# HC_SR04_SCH.net
KiCad netlist of a schematic drawn in Altium Designer
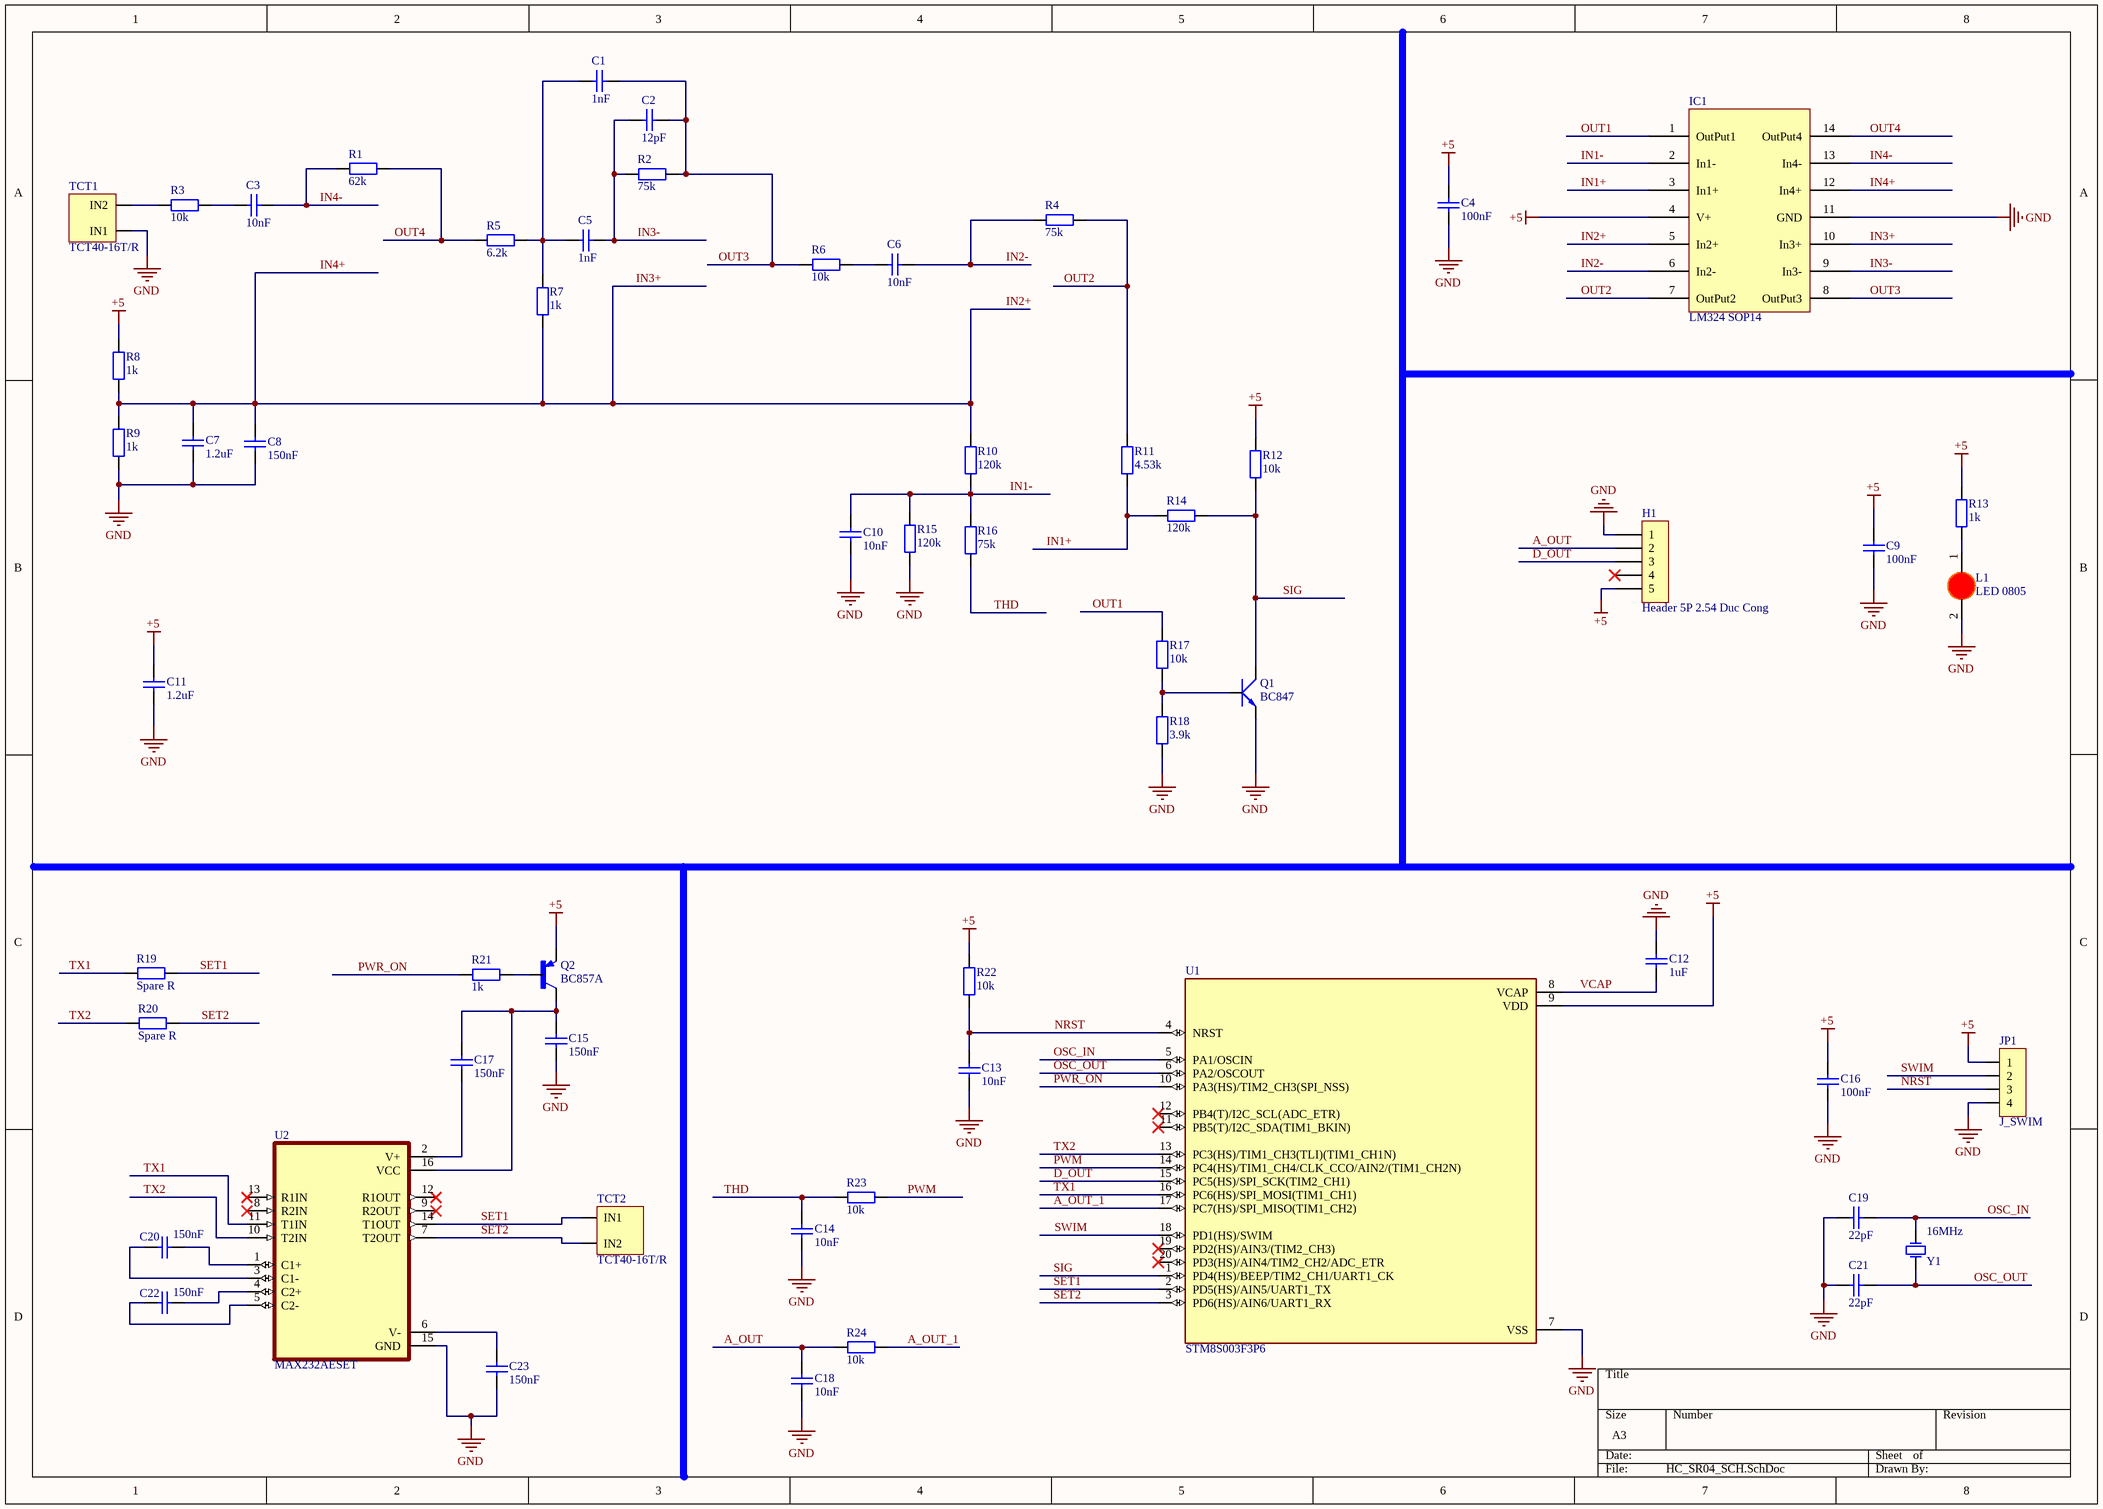
[diagram p0: HC_SR04_SCH.SchDoc]

(export (version "E")
  (design (tool "Eeschema 10.0.6"))
  (components
    (comp (ref "C1")
      (value "1nF")
      (footprint "tu 0603")
      (description "Dán")
      (libsource (lib "namnt_Lib") (part "Tu 0603 102 50V 10%"))
    )
    (comp (ref "C2")
      (value "12pF")
      (footprint "tu 0603")
      (description "Dán")
      (libsource (lib "namnt_Lib") (part "Tu 0603 102 50V 10%"))
    )
    (comp (ref "C3")
      (value "10nF")
      (footprint "tu 0603")
      (description "Dán")
      (libsource (lib "namnt_Lib") (part "Tu 0603 103 50V 10%"))
    )
    (comp (ref "C4")
      (value "100nF")
      (footprint "tu 0603")
      (description "Dán")
      (libsource (lib "namnt_Lib") (part "Tu 0603 102 50V 10%"))
    )
    (comp (ref "C5")
      (value "1nF")
      (footprint "tu 0603")
      (description "Dán")
      (libsource (lib "namnt_Lib") (part "Tu 0603 102 50V 10%"))
    )
    (comp (ref "C6")
      (value "10nF")
      (footprint "tu 0603")
      (description "Dán")
      (libsource (lib "namnt_Lib") (part "Tu 0603 102 50V 10%"))
    )
    (comp (ref "C7")
      (value "1.2uF")
      (footprint "tu 0603")
      (description "Dán")
      (libsource (lib "namnt_Lib") (part "Tu 0603 104 50V 10%"))
    )
    (comp (ref "C8")
      (value "150nF")
      (footprint "tu 0603")
      (description "Dán")
      (libsource (lib "namnt_Lib") (part "Tu 0603 104 50V 10%"))
    )
    (comp (ref "C9")
      (value "100nF")
      (footprint "tu 0603")
      (description "Dán")
      (libsource (lib "namnt_Lib") (part "Tu 0603 102 50V 10%"))
    )
    (comp (ref "C10")
      (value "10nF")
      (footprint "tu 0603")
      (description "Dán")
      (libsource (lib "namnt_Lib") (part "Tu 0603 102 50V 10%"))
    )
    (comp (ref "C11")
      (value "1.2uF")
      (footprint "tu 0603")
      (description "Dán")
      (libsource (lib "namnt_Lib") (part "Tu 0603 102 50V 10%"))
    )
    (comp (ref "C12")
      (value "1uF")
      (footprint "tu 0603")
      (description "Dán")
      (libsource (lib "namnt_Lib") (part "Tu 0603 102 50V 10%"))
    )
    (comp (ref "C13")
      (value "10nF")
      (footprint "tu 0603")
      (description "Dán")
      (libsource (lib "namnt_Lib") (part "Tu 0603 102 50V 10%"))
    )
    (comp (ref "C14")
      (value "10nF")
      (footprint "tu 0603")
      (description "Dán")
      (libsource (lib "namnt_Lib") (part "Tu 0603 102 50V 10%"))
    )
    (comp (ref "C15")
      (value "150nF")
      (footprint "tu 0603")
      (description "Dán")
      (libsource (lib "namnt_Lib") (part "Tu 0603 102 50V 10%"))
    )
    (comp (ref "C16")
      (value "100nF")
      (footprint "tu 0603")
      (description "Dán")
      (libsource (lib "namnt_Lib") (part "Tu 0603 102 50V 10%"))
    )
    (comp (ref "C17")
      (value "150nF")
      (footprint "tu 0603")
      (description "Dán")
      (libsource (lib "namnt_Lib") (part "Tu 0603 102 50V 10%"))
    )
    (comp (ref "C18")
      (value "10nF")
      (footprint "tu 0603")
      (description "Dán")
      (libsource (lib "namnt_Lib") (part "Tu 0603 102 50V 10%"))
    )
    (comp (ref "C19")
      (value "22pF")
      (footprint "tu 0603")
      (description "Dán")
      (libsource (lib "namnt_Lib") (part "Tu 0603 102 50V 10%"))
    )
    (comp (ref "C20")
      (value "150nF")
      (footprint "tu 0603")
      (description "Dán")
      (libsource (lib "namnt_Lib") (part "Tu 0603 102 50V 10%"))
    )
    (comp (ref "C21")
      (value "22pF")
      (footprint "tu 0603")
      (description "Dán")
      (libsource (lib "namnt_Lib") (part "Tu 0603 102 50V 10%"))
    )
    (comp (ref "C22")
      (value "150nF")
      (footprint "tu 0603")
      (description "Dán")
      (libsource (lib "namnt_Lib") (part "Tu 0603 102 50V 10%"))
    )
    (comp (ref "C23")
      (value "150nF")
      (footprint "tu 0603")
      (description "Dán")
      (libsource (lib "namnt_Lib") (part "Tu 0603 102 50V 10%"))
    )
    (comp (ref "H1")
      (value "Header 5P 2.54 Duc Cong")
      (footprint "Header 5P DC 2.54")
      (description "Cắm")
      (libsource (lib "namnt_Lib") (part "Header 5P 2.54 Duc Cong"))
    )
    (comp (ref "IC1")
      (value "LM324 SOP14")
      (footprint "sop 14")
      (description "Dán")
      (libsource (lib "namnt_Lib") (part "LM324 SOP14"))
    )
    (comp (ref "JP1")
      (value "J_SWIM")
      (footprint "JP 1x4 DT")
      (description "Cắm")
      (libsource (lib "namnt_Lib") (part "JP 1x4 2.54 Duc Thang"))
    )
    (comp (ref "L1")
      (value "LED 0805")
      (footprint "LED-0805-Red")
      (description "Dán")
      (libsource (lib "namnt_Lib") (part "LED 0805 Do"))
    )
    (comp (ref "Q1")
      (value "BC847")
      (footprint "SOT-23")
      (description "SOT-23")
      (libsource (lib "namnt_Lib") (part "Trans BC817"))
    )
    (comp (ref "Q2")
      (value "BC857A")
      (footprint "TRANS_BC857A_RFG")
      (description "SOT-23, 200mW, PNP Bipolar Transistor")
      (fields (field (name "MF") "Taiwan Semiconductor") (field (name "MP") "BC857A RFG"))
      (libsource (lib "namnt_Lib") (part "BC857A_RFG"))
    )
    (comp (ref "R1")
      (value "62k")
      (footprint "tro smd 0603")
      (description "Dán")
      (libsource (lib "namnt_Lib") (part "Tro 0603 1% 1k"))
    )
    (comp (ref "R2")
      (value "75k")
      (footprint "tro smd 0603")
      (description "Dán")
      (libsource (lib "namnt_Lib") (part "Tro 0603 1% 1k"))
    )
    (comp (ref "R3")
      (value "10k")
      (footprint "tro smd 0603")
      (description "Dán")
      (libsource (lib "namnt_Lib") (part "Tro 0603 1% 10k"))
    )
    (comp (ref "R4")
      (value "75k")
      (footprint "tro smd 0603")
      (description "Dán")
      (libsource (lib "namnt_Lib") (part "Tro 0603 1% 1k"))
    )
    (comp (ref "R5")
      (value "6.2k")
      (footprint "tro smd 0603")
      (description "Dán")
      (libsource (lib "namnt_Lib") (part "Tro 0603 1% 1k"))
    )
    (comp (ref "R6")
      (value "10k")
      (footprint "tro smd 0603")
      (description "Dán")
      (libsource (lib "namnt_Lib") (part "Tro 0603 1% 1k"))
    )
    (comp (ref "R7")
      (value "1k")
      (footprint "tro smd 0603")
      (description "Dán")
      (libsource (lib "namnt_Lib") (part "Tro 0603 1% 1k"))
    )
    (comp (ref "R8")
      (value "1k")
      (footprint "tro smd 0603")
      (description "Dán")
      (libsource (lib "namnt_Lib") (part "Tro 0603 1% 1k"))
    )
    (comp (ref "R9")
      (value "1k")
      (footprint "tro smd 0603")
      (description "Dán")
      (libsource (lib "namnt_Lib") (part "Tro 0603 1% 1k"))
    )
    (comp (ref "R10")
      (value "120k")
      (footprint "tro smd 0603")
      (description "Dán")
      (libsource (lib "namnt_Lib") (part "Tro 0603 1% 1k"))
    )
    (comp (ref "R11")
      (value "4.53k")
      (footprint "tro smd 0603")
      (description "Dán")
      (libsource (lib "namnt_Lib") (part "Tro 0603 1% 1k"))
    )
    (comp (ref "R12")
      (value "10k")
      (footprint "tro smd 0603")
      (description "Dán")
      (libsource (lib "namnt_Lib") (part "Tro 0603 1% 1k"))
    )
    (comp (ref "R13")
      (value "1k")
      (footprint "tro smd 0603")
      (description "Dán")
      (libsource (lib "namnt_Lib") (part "Tro 0603 1% 1k"))
    )
    (comp (ref "R14")
      (value "120k")
      (footprint "tro smd 0603")
      (description "Dán")
      (libsource (lib "namnt_Lib") (part "Tro 0603 1% 1k"))
    )
    (comp (ref "R15")
      (value "120k")
      (footprint "tro smd 0603")
      (description "Dán")
      (libsource (lib "namnt_Lib") (part "Tro 0603 1% 1k"))
    )
    (comp (ref "R16")
      (value "75k")
      (footprint "tro smd 0603")
      (description "Dán")
      (libsource (lib "namnt_Lib") (part "Tro 0603 1% 1k"))
    )
    (comp (ref "R17")
      (value "10k")
      (footprint "tro smd 0603")
      (description "Dán")
      (libsource (lib "namnt_Lib") (part "Tro 0603 1% 1k"))
    )
    (comp (ref "R18")
      (value "3.9k")
      (footprint "tro smd 0603")
      (description "Dán")
      (libsource (lib "namnt_Lib") (part "Tro 0603 1% 1k"))
    )
    (comp (ref "R19")
      (value "Spare R")
      (footprint "tro smd 0603")
      (description "Dán")
      (libsource (lib "namnt_Lib") (part "Tro 0603 1% 1k"))
    )
    (comp (ref "R20")
      (value "Spare R")
      (footprint "tro smd 0603")
      (description "Dán")
      (libsource (lib "namnt_Lib") (part "Tro 0603 1% 1k"))
    )
    (comp (ref "R21")
      (value "1k")
      (footprint "tro smd 0603")
      (description "Dán")
      (libsource (lib "namnt_Lib") (part "Tro 0603 1% 1k"))
    )
    (comp (ref "R22")
      (value "10k")
      (footprint "tro smd 0603")
      (description "Dán")
      (libsource (lib "namnt_Lib") (part "Tro 0603 1% 1k"))
    )
    (comp (ref "R23")
      (value "10k")
      (footprint "tro smd 0603")
      (description "Dán")
      (libsource (lib "namnt_Lib") (part "Tro 0603 1% 1k"))
    )
    (comp (ref "R24")
      (value "10k")
      (footprint "tro smd 0603")
      (description "Dán")
      (libsource (lib "namnt_Lib") (part "Tro 0603 1% 1k"))
    )
    (comp (ref "TCT1")
      (value "TCT40-16T/R")
      (footprint "TCT40")
      (description "Piezoelectric Ceramic Ultrasonic Sensor")
      (libsource (lib "") (part "TCT40-16T/R_1"))
    )
    (comp (ref "TCT2")
      (value "TCT40-16T/R")
      (footprint "TCT40")
      (description "Piezoelectric Ceramic Ultrasonic Sensor")
      (libsource (lib "namnt_Lib") (part "TCT40-16T/R"))
    )
    (comp (ref "U1")
      (value "STM8S003F3P6")
      (footprint "SOP65P640X120-20N")
      (description "STM8 series Microcontroller IC 8-Bit 16MHz 8KB (8K x 8) FLASH 20-TSSOP")
      (fields (field (name "MF") "STMicroelectronics"))
      (libsource (lib "namnt_Lib") (part "STM8S003F3P6"))
    )
    (comp (ref "U2")
      (value "MAX232AESET")
      (footprint "SOIC127P600X175-16N")
      (description "Dual Transmitter/Receiver RS-232 16-Pin SOIC N Tube")
      (fields (field (name "MF") "Analog Devices") (field (name "MP") "MAX232AESE+"))
      (libsource (lib "namnt_Lib") (part "MAX232AESET"))
    )
    (comp (ref "Y1")
      (value "16MHz")
      (footprint "THACH ANH DAN 3215")
      (description "C700805")
      (libsource (lib "namnt_Lib") (part "Thach Anh SMD 3225"))
    )
  )
  (nets
    (net (code "1") (name "+5") (class "Default")
      (node (ref "C11") (pin "1") (pinfunction "1_1") (pintype "passive"))
      (node (ref "C16") (pin "1") (pinfunction "1_1") (pintype "passive"))
      (node (ref "C4") (pin "1") (pinfunction "1_1") (pintype "passive"))
      (node (ref "C9") (pin "1") (pinfunction "1_1") (pintype "passive"))
      (node (ref "H1") (pin "5") (pinfunction "5_5") (pintype "passive"))
      (node (ref "IC1") (pin "4") (pinfunction "V+_4") (pintype "passive"))
      (node (ref "JP1") (pin "1") (pinfunction "1_1") (pintype "passive"))
      (node (ref "Q2") (pin "2") (pinfunction "E_2") (pintype "passive"))
      (node (ref "R12") (pin "2") (pinfunction "2_2") (pintype "passive"))
      (node (ref "R13") (pin "2") (pinfunction "2_2") (pintype "passive"))
      (node (ref "R22") (pin "1") (pinfunction "1_1") (pintype "passive"))
      (node (ref "R8") (pin "2") (pinfunction "2_2") (pintype "passive"))
      (node (ref "U1") (pin "9") (pinfunction "VDD_9") (pintype "power_in"))
    )
    (net (code "2") (name "/A_OUT") (class "Default")
      (node (ref "C18") (pin "1") (pinfunction "1_1") (pintype "passive"))
      (node (ref "H1") (pin "2") (pinfunction "2_2") (pintype "passive"))
      (node (ref "R24") (pin "2") (pinfunction "2_2") (pintype "passive"))
    )
    (net (code "3") (name "/A_OUT_1") (class "Default")
      (node (ref "R24") (pin "1") (pinfunction "1_1") (pintype "passive"))
      (node (ref "U1") (pin "17") (pinfunction "PC7(HS)/SPI_MISO(TIM1_CH2)_17") (pintype "bidirectional"))
    )
    (net (code "4") (name "/D_OUT") (class "Default")
      (node (ref "H1") (pin "3") (pinfunction "3_3") (pintype "passive"))
      (node (ref "U1") (pin "15") (pinfunction "PC5(HS)/SPI_SCK(TIM2_CH1)_15") (pintype "bidirectional"))
    )
    (net (code "5") (name "/IN1+") (class "Default")
      (node (ref "IC1") (pin "3") (pinfunction "In1+_3") (pintype "passive"))
      (node (ref "R11") (pin "2") (pinfunction "2_2") (pintype "passive"))
      (node (ref "R14") (pin "1") (pinfunction "1_1") (pintype "passive"))
    )
    (net (code "6") (name "/IN1-") (class "Default")
      (node (ref "C10") (pin "1") (pinfunction "1_1") (pintype "passive"))
      (node (ref "IC1") (pin "2") (pinfunction "In1-_2") (pintype "passive"))
      (node (ref "R10") (pin "2") (pinfunction "2_2") (pintype "passive"))
      (node (ref "R15") (pin "2") (pinfunction "2_2") (pintype "passive"))
      (node (ref "R16") (pin "2") (pinfunction "2_2") (pintype "passive"))
    )
    (net (code "7") (name "/IN2+") (class "Default")
      (node (ref "C7") (pin "1") (pinfunction "1_1") (pintype "passive"))
      (node (ref "C8") (pin "1") (pinfunction "1_1") (pintype "passive"))
      (node (ref "IC1") (pin "10") (pinfunction "In3+_10") (pintype "passive"))
      (node (ref "IC1") (pin "12") (pinfunction "In4+_12") (pintype "passive"))
      (node (ref "IC1") (pin "5") (pinfunction "In2+_5") (pintype "passive"))
      (node (ref "R10") (pin "1") (pinfunction "1_1") (pintype "passive"))
      (node (ref "R7") (pin "2") (pinfunction "2_2") (pintype "passive"))
      (node (ref "R8") (pin "1") (pinfunction "1_1") (pintype "passive"))
      (node (ref "R9") (pin "2") (pinfunction "2_2") (pintype "passive"))
    )
    (net (code "8") (name "/IN2-") (class "Default")
      (node (ref "C6") (pin "1") (pinfunction "1_1") (pintype "passive"))
      (node (ref "IC1") (pin "6") (pinfunction "In2-_6") (pintype "passive"))
      (node (ref "R4") (pin "2") (pinfunction "2_2") (pintype "passive"))
    )
    (net (code "9") (name "/IN3-") (class "Default")
      (node (ref "C2") (pin "2") (pinfunction "2_2") (pintype "passive"))
      (node (ref "C5") (pin "1") (pinfunction "1_1") (pintype "passive"))
      (node (ref "IC1") (pin "9") (pinfunction "In3-_9") (pintype "passive"))
      (node (ref "R2") (pin "2") (pinfunction "2_2") (pintype "passive"))
    )
    (net (code "10") (name "/IN4-") (class "Default")
      (node (ref "C3") (pin "2") (pinfunction "2_2") (pintype "passive"))
      (node (ref "IC1") (pin "13") (pinfunction "In4-_13") (pintype "passive"))
      (node (ref "R1") (pin "2") (pinfunction "2_2") (pintype "passive"))
    )
    (net (code "11") (name "/NRST") (class "Default")
      (node (ref "C13") (pin "1") (pinfunction "1_1") (pintype "passive"))
      (node (ref "JP1") (pin "3") (pinfunction "3_3") (pintype "passive"))
      (node (ref "R22") (pin "2") (pinfunction "2_2") (pintype "passive"))
      (node (ref "U1") (pin "4") (pinfunction "NRST_4") (pintype "bidirectional"))
    )
    (net (code "12") (name "/OSC_IN") (class "Default")
      (node (ref "C19") (pin "2") (pinfunction "2_2") (pintype "passive"))
      (node (ref "U1") (pin "5") (pinfunction "PA1/OSCIN_5") (pintype "bidirectional"))
      (node (ref "Y1") (pin "2") (pinfunction "OSC2_2") (pintype "passive"))
    )
    (net (code "13") (name "/OSC_OUT") (class "Default")
      (node (ref "C21") (pin "2") (pinfunction "2_2") (pintype "passive"))
      (node (ref "U1") (pin "6") (pinfunction "PA2/OSCOUT_6") (pintype "bidirectional"))
      (node (ref "Y1") (pin "1") (pinfunction "OSC1_1") (pintype "passive"))
    )
    (net (code "14") (name "/OUT1") (class "Default")
      (node (ref "IC1") (pin "1") (pinfunction "OutPut1_1") (pintype "passive"))
      (node (ref "R17") (pin "2") (pinfunction "2_2") (pintype "passive"))
    )
    (net (code "15") (name "/OUT2") (class "Default")
      (node (ref "IC1") (pin "7") (pinfunction "OutPut2_7") (pintype "passive"))
      (node (ref "R11") (pin "1") (pinfunction "1_1") (pintype "passive"))
      (node (ref "R4") (pin "1") (pinfunction "1_1") (pintype "passive"))
    )
    (net (code "16") (name "/OUT3") (class "Default")
      (node (ref "C1") (pin "1") (pinfunction "1_1") (pintype "passive"))
      (node (ref "C2") (pin "1") (pinfunction "1_1") (pintype "passive"))
      (node (ref "IC1") (pin "8") (pinfunction "OutPut3_8") (pintype "passive"))
      (node (ref "R2") (pin "1") (pinfunction "1_1") (pintype "passive"))
      (node (ref "R6") (pin "2") (pinfunction "2_2") (pintype "passive"))
    )
    (net (code "17") (name "/OUT4") (class "Default")
      (node (ref "IC1") (pin "14") (pinfunction "OutPut4_14") (pintype "passive"))
      (node (ref "R1") (pin "1") (pinfunction "1_1") (pintype "passive"))
      (node (ref "R5") (pin "2") (pinfunction "2_2") (pintype "passive"))
    )
    (net (code "18") (name "/PWM") (class "Default")
      (node (ref "R23") (pin "1") (pinfunction "1_1") (pintype "passive"))
      (node (ref "U1") (pin "14") (pinfunction "PC4(HS)/TIM1_CH4/CLK_CCO/AIN2/(TIM1_CH2N)_14") (pintype "bidirectional"))
    )
    (net (code "19") (name "/PWR_ON") (class "Default")
      (node (ref "R21") (pin "2") (pinfunction "2_2") (pintype "passive"))
      (node (ref "U1") (pin "10") (pinfunction "PA3(HS)/TIM2_CH3(SPI_NSS)_10") (pintype "bidirectional"))
    )
    (net (code "20") (name "/SET1") (class "Default")
      (node (ref "R19") (pin "2") (pinfunction "2_2") (pintype "passive"))
      (node (ref "TCT2") (pin "1") (pinfunction "IN1_1") (pintype "passive"))
      (node (ref "U1") (pin "2") (pinfunction "PD5(HS)/AIN5/UART1_TX_2") (pintype "bidirectional"))
      (node (ref "U2") (pin "14") (pinfunction "T1OUT_14") (pintype "output"))
    )
    (net (code "21") (name "/SET2") (class "Default")
      (node (ref "R20") (pin "2") (pinfunction "2_2") (pintype "passive"))
      (node (ref "TCT2") (pin "2") (pinfunction "IN2_2") (pintype "passive"))
      (node (ref "U1") (pin "3") (pinfunction "PD6(HS)/AIN6/UART1_RX_3") (pintype "bidirectional"))
      (node (ref "U2") (pin "7") (pinfunction "T2OUT_7") (pintype "output"))
    )
    (net (code "22") (name "/SIG") (class "Default")
      (node (ref "Q1") (pin "3") (pinfunction "C_3") (pintype "passive"))
      (node (ref "R12") (pin "1") (pinfunction "1_1") (pintype "passive"))
      (node (ref "R14") (pin "2") (pinfunction "2_2") (pintype "passive"))
      (node (ref "U1") (pin "1") (pinfunction "PD4(HS)/BEEP/TIM2_CH1/UART1_CK_1") (pintype "bidirectional"))
    )
    (net (code "23") (name "/SWIM") (class "Default")
      (node (ref "JP1") (pin "2") (pinfunction "2_2") (pintype "passive"))
      (node (ref "U1") (pin "18") (pinfunction "PD1(HS)/SWIM_18") (pintype "bidirectional"))
    )
    (net (code "24") (name "/THD") (class "Default")
      (node (ref "C14") (pin "1") (pinfunction "1_1") (pintype "passive"))
      (node (ref "R16") (pin "1") (pinfunction "1_1") (pintype "passive"))
      (node (ref "R23") (pin "2") (pinfunction "2_2") (pintype "passive"))
    )
    (net (code "25") (name "/TX1") (class "Default")
      (node (ref "R19") (pin "1") (pinfunction "1_1") (pintype "passive"))
      (node (ref "U1") (pin "16") (pinfunction "PC6(HS)/SPI_MOSI(TIM1_CH1)_16") (pintype "bidirectional"))
      (node (ref "U2") (pin "11") (pinfunction "T1IN_11") (pintype "input"))
    )
    (net (code "26") (name "/TX2") (class "Default")
      (node (ref "R20") (pin "1") (pinfunction "1_1") (pintype "passive"))
      (node (ref "U1") (pin "13") (pinfunction "PC3(HS)/TIM1_CH3(TLI)(TIM1_CH1N)_13") (pintype "bidirectional"))
      (node (ref "U2") (pin "10") (pinfunction "T2IN_10") (pintype "input"))
    )
    (net (code "27") (name "/VCAP") (class "Default")
      (node (ref "C12") (pin "2") (pinfunction "2_2") (pintype "passive"))
      (node (ref "U1") (pin "8") (pinfunction "VCAP_8") (pintype "power_in"))
    )
    (net (code "28") (name "GND") (class "Default")
      (node (ref "C10") (pin "2") (pinfunction "2_2") (pintype "passive"))
      (node (ref "C11") (pin "2") (pinfunction "2_2") (pintype "passive"))
      (node (ref "C12") (pin "1") (pinfunction "1_1") (pintype "passive"))
      (node (ref "C13") (pin "2") (pinfunction "2_2") (pintype "passive"))
      (node (ref "C14") (pin "2") (pinfunction "2_2") (pintype "passive"))
      (node (ref "C15") (pin "2") (pinfunction "2_2") (pintype "passive"))
      (node (ref "C16") (pin "2") (pinfunction "2_2") (pintype "passive"))
      (node (ref "C18") (pin "2") (pinfunction "2_2") (pintype "passive"))
      (node (ref "C19") (pin "1") (pinfunction "1_1") (pintype "passive"))
      (node (ref "C21") (pin "1") (pinfunction "1_1") (pintype "passive"))
      (node (ref "C23") (pin "2") (pinfunction "2_2") (pintype "passive"))
      (node (ref "C4") (pin "2") (pinfunction "2_2") (pintype "passive"))
      (node (ref "C7") (pin "2") (pinfunction "2_2") (pintype "passive"))
      (node (ref "C8") (pin "2") (pinfunction "2_2") (pintype "passive"))
      (node (ref "C9") (pin "2") (pinfunction "2_2") (pintype "passive"))
      (node (ref "H1") (pin "1") (pinfunction "1_1") (pintype "passive"))
      (node (ref "IC1") (pin "11") (pinfunction "GND_11") (pintype "passive"))
      (node (ref "JP1") (pin "4") (pinfunction "4_4") (pintype "passive"))
      (node (ref "L1") (pin "2") (pinfunction "K_2") (pintype "passive"))
      (node (ref "Q1") (pin "2") (pinfunction "E_2") (pintype "passive"))
      (node (ref "R15") (pin "1") (pinfunction "1_1") (pintype "passive"))
      (node (ref "R18") (pin "1") (pinfunction "1_1") (pintype "passive"))
      (node (ref "R9") (pin "1") (pinfunction "1_1") (pintype "passive"))
      (node (ref "TCT1") (pin "1") (pinfunction "IN1_1") (pintype "passive"))
      (node (ref "U1") (pin "7") (pinfunction "VSS_7") (pintype "power_in"))
      (node (ref "U2") (pin "15") (pinfunction "GND_15") (pintype "power_in"))
    )
    (net (code "29") (name "Net-(C1-Pad2)") (class "Default")
      (node (ref "C1") (pin "2") (pinfunction "2_2") (pintype "passive"))
      (node (ref "C5") (pin "2") (pinfunction "2_2") (pintype "passive"))
      (node (ref "R5") (pin "1") (pinfunction "1_1") (pintype "passive"))
      (node (ref "R7") (pin "1") (pinfunction "1_1") (pintype "passive"))
    )
    (net (code "30") (name "Net-(C3-Pad1)") (class "Default")
      (node (ref "C3") (pin "1") (pinfunction "1_1") (pintype "passive"))
      (node (ref "R3") (pin "2") (pinfunction "2_2") (pintype "passive"))
    )
    (net (code "31") (name "Net-(C6-Pad2)") (class "Default")
      (node (ref "C6") (pin "2") (pinfunction "2_2") (pintype "passive"))
      (node (ref "R6") (pin "1") (pinfunction "1_1") (pintype "passive"))
    )
    (net (code "32") (name "Net-(L1-A)") (class "Default")
      (node (ref "L1") (pin "1") (pinfunction "A_1") (pintype "passive"))
      (node (ref "R13") (pin "1") (pinfunction "1_1") (pintype "passive"))
    )
    (net (code "33") (name "Net-(Q1-B)") (class "Default")
      (node (ref "Q1") (pin "1") (pinfunction "B_1") (pintype "passive"))
      (node (ref "R17") (pin "1") (pinfunction "1_1") (pintype "passive"))
      (node (ref "R18") (pin "2") (pinfunction "2_2") (pintype "passive"))
    )
    (net (code "34") (name "Net-(Q2-B)") (class "Default")
      (node (ref "Q2") (pin "1") (pinfunction "B_1") (pintype "passive"))
      (node (ref "R21") (pin "1") (pinfunction "1_1") (pintype "passive"))
    )
    (net (code "35") (name "Net-(Q2-C)") (class "Default")
      (node (ref "C15") (pin "1") (pinfunction "1_1") (pintype "passive"))
      (node (ref "C17") (pin "1") (pinfunction "1_1") (pintype "passive"))
      (node (ref "Q2") (pin "3") (pinfunction "C_3") (pintype "passive"))
      (node (ref "U2") (pin "16") (pinfunction "VCC_16") (pintype "power_in"))
    )
    (net (code "36") (name "Net-(TCT1-IN2)") (class "Default")
      (node (ref "R3") (pin "1") (pinfunction "1_1") (pintype "passive"))
      (node (ref "TCT1") (pin "2") (pinfunction "IN2_2") (pintype "passive"))
    )
    (net (code "37") (name "Net-(U2-C1+)") (class "Default")
      (node (ref "C20") (pin "2") (pinfunction "2_2") (pintype "passive"))
      (node (ref "U2") (pin "1") (pinfunction "C1+_1") (pintype "bidirectional"))
    )
    (net (code "38") (name "Net-(U2-C1-)") (class "Default")
      (node (ref "C20") (pin "1") (pinfunction "1_1") (pintype "passive"))
      (node (ref "U2") (pin "3") (pinfunction "C1-_3") (pintype "bidirectional"))
    )
    (net (code "39") (name "Net-(U2-C2+)") (class "Default")
      (node (ref "C22") (pin "2") (pinfunction "2_2") (pintype "passive"))
      (node (ref "U2") (pin "4") (pinfunction "C2+_4") (pintype "bidirectional"))
    )
    (net (code "40") (name "Net-(U2-C2-)") (class "Default")
      (node (ref "C22") (pin "1") (pinfunction "1_1") (pintype "passive"))
      (node (ref "U2") (pin "5") (pinfunction "C2-_5") (pintype "bidirectional"))
    )
    (net (code "41") (name "Net-(U2-V+)") (class "Default")
      (node (ref "C17") (pin "2") (pinfunction "2_2") (pintype "passive"))
      (node (ref "U2") (pin "2") (pinfunction "V+_2") (pintype "power_in"))
    )
    (net (code "42") (name "Net-(U2-V-)") (class "Default")
      (node (ref "C23") (pin "1") (pinfunction "1_1") (pintype "passive"))
      (node (ref "U2") (pin "6") (pinfunction "V-_6") (pintype "power_in"))
    )
    (net (code "43") (name "unconnected-(H1-Pad4)") (class "Default")
      (node (ref "H1") (pin "4") (pinfunction "4_4") (pintype "passive+no_connect"))
    )
    (net (code "44") (name "unconnected-(U1-PB4(T){slash}I2C_SCL(ADC_ETR)-Pad12)") (class "Default")
      (node (ref "U1") (pin "12") (pinfunction "PB4(T)/I2C_SCL(ADC_ETR)_12") (pintype "bidirectional+no_connect"))
    )
    (net (code "45") (name "unconnected-(U1-PB5(T){slash}I2C_SDA(TIM1_BKIN)-Pad11)") (class "Default")
      (node (ref "U1") (pin "11") (pinfunction "PB5(T)/I2C_SDA(TIM1_BKIN)_11") (pintype "bidirectional+no_connect"))
    )
    (net (code "46") (name "unconnected-(U1-PD2(HS){slash}AIN3{slash}(TIM2_CH3)-Pad19)") (class "Default")
      (node (ref "U1") (pin "19") (pinfunction "PD2(HS)/AIN3/(TIM2_CH3)_19") (pintype "bidirectional+no_connect"))
    )
    (net (code "47") (name "unconnected-(U1-PD3(HS){slash}AIN4{slash}TIM2_CH2{slash}ADC_ETR-Pad20)") (class "Default")
      (node (ref "U1") (pin "20") (pinfunction "PD3(HS)/AIN4/TIM2_CH2/ADC_ETR_20") (pintype "bidirectional+no_connect"))
    )
    (net (code "48") (name "unconnected-(U2-R1IN-Pad13)") (class "Default")
      (node (ref "U2") (pin "13") (pinfunction "R1IN_13") (pintype "input+no_connect"))
    )
    (net (code "49") (name "unconnected-(U2-R1OUT-Pad12)") (class "Default")
      (node (ref "U2") (pin "12") (pinfunction "R1OUT_12") (pintype "output+no_connect"))
    )
    (net (code "50") (name "unconnected-(U2-R2IN-Pad8)") (class "Default")
      (node (ref "U2") (pin "8") (pinfunction "R2IN_8") (pintype "input+no_connect"))
    )
    (net (code "51") (name "unconnected-(U2-R2OUT-Pad9)") (class "Default")
      (node (ref "U2") (pin "9") (pinfunction "R2OUT_9") (pintype "output+no_connect"))
    )
  )
)
